# IC_Power.net
KiCad netlist of a schematic drawn in Altium Designer
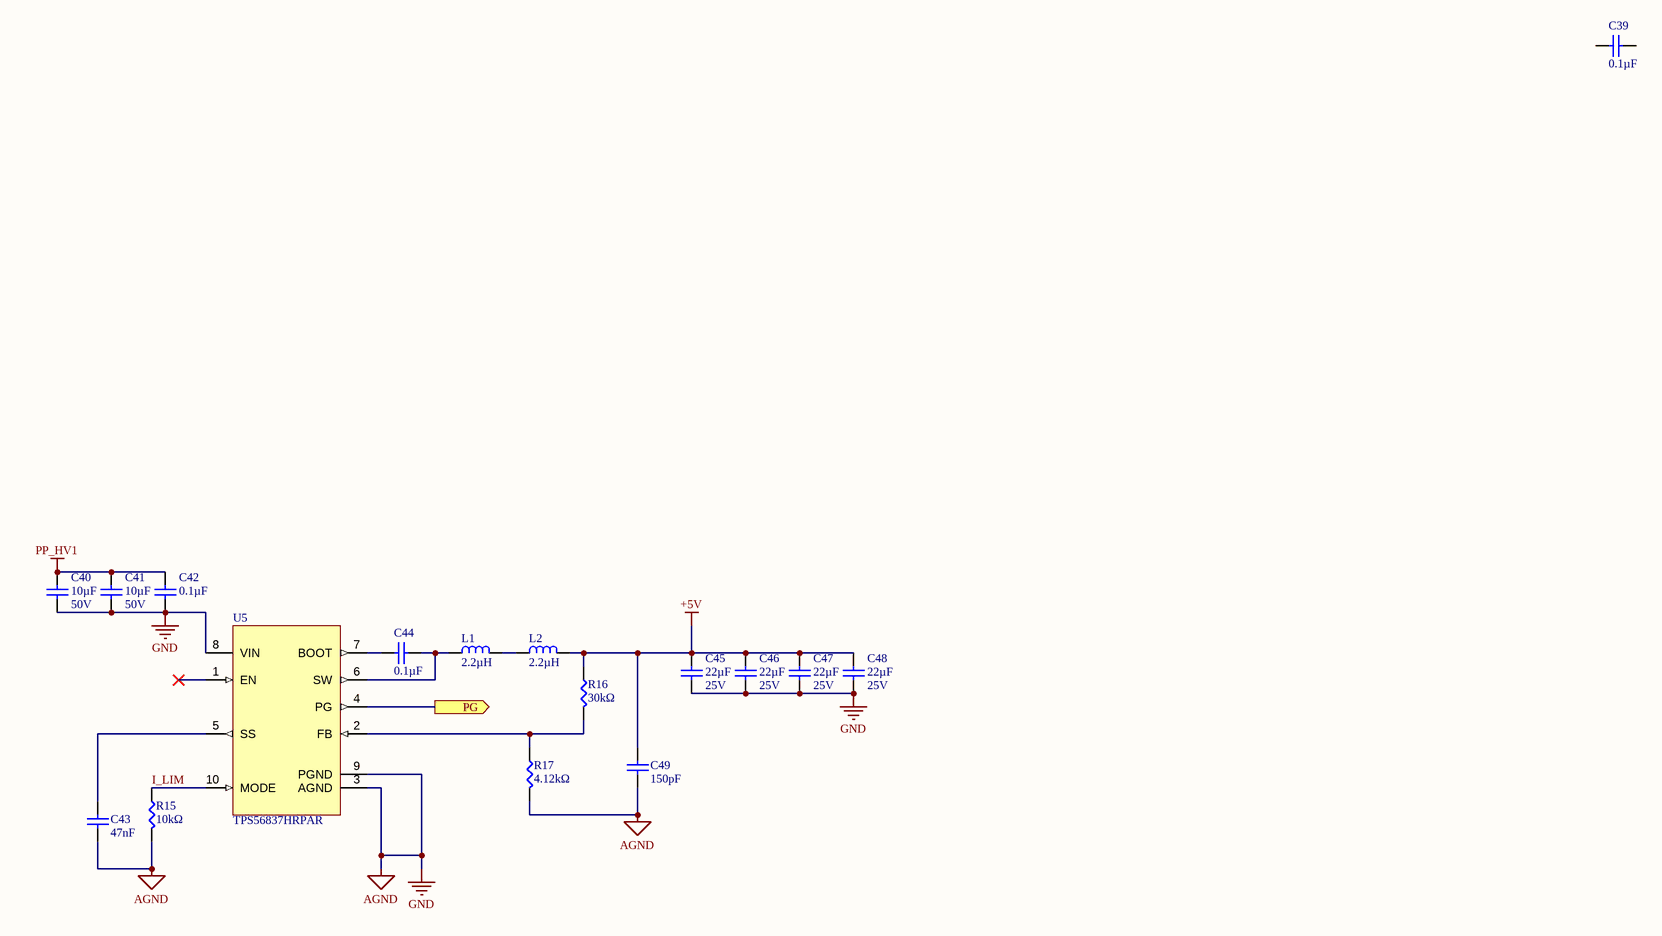
[diagram p0: IC_Power.SchDoc]

(export (version "E")
  (design (tool "Eeschema 10.0.6"))
  (components
    (comp (ref "C39")
      (value "0.1µF")
      (footprint "CAP0402")
      (description "0.1 µF ±10% 50V Ceramic Capacitor X5R 0402 (1005 Metric)")
      (fields (field (name "VOLTAGE") "50V") (field (name "Comment") "CC0402KRX5R9BB104"))
      (libsource (lib "Schlib1") (part "CC0402KRX5R9BB104"))
    )
    (comp (ref "C40")
      (value "10µF")
      (footprint "CAP1206")
      (description "10 µF ±10% 50V Ceramic Capacitor X5R 1206 (3216 Metric)")
      (fields (field (name "VOLTAGE") "50V") (field (name "Comment") "CL31A106KBHNNNE"))
      (libsource (lib "Schlib1") (part "CL31A106KBHNNNE"))
    )
    (comp (ref "C41")
      (value "10µF")
      (footprint "CAP1206")
      (description "10 µF ±10% 50V Ceramic Capacitor X5R 1206 (3216 Metric)")
      (fields (field (name "VOLTAGE") "50V") (field (name "Comment") "CL31A106KBHNNNE"))
      (libsource (lib "Schlib1") (part "CL31A106KBHNNNE"))
    )
    (comp (ref "C42")
      (value "0.1µF")
      (footprint "CAP0402")
      (description "0.1 µF ±10% 50V Ceramic Capacitor X5R 0402 (1005 Metric)")
      (fields (field (name "VOLTAGE") "50V") (field (name "Comment") "CC0402KRX5R9BB104"))
      (libsource (lib "Schlib1") (part "CC0402KRX5R9BB104"))
    )
    (comp (ref "C43")
      (value "47nF")
      (footprint "CAP0402")
      (description "0.047 µF ±10% 50V Ceramic Capacitor X7R 0402 (1005 Metric)")
      (fields (field (name "VOLTAGE") "50V") (field (name "Comment") "GRM155R71H473KE14D"))
      (libsource (lib "Schlib1") (part "GRM155R71H473KE14D"))
    )
    (comp (ref "C44")
      (value "0.1µF")
      (footprint "CAP0402")
      (description "0.1 µF ±10% 50V Ceramic Capacitor X5R 0402 (1005 Metric)")
      (fields (field (name "VOLTAGE") "50V") (field (name "Comment") "CC0402KRX5R9BB104"))
      (libsource (lib "Schlib1") (part "CC0402KRX5R9BB104"))
    )
    (comp (ref "C45")
      (value "22µF")
      (footprint "CAP0805")
      (description "22 µF ±20% 25V Ceramic Capacitor X5R 0805 (2012 Metric)")
      (fields (field (name "VOLTAGE") "25V") (field (name "Comment") "CL21A226MAYNNNE"))
      (libsource (lib "Schlib1") (part "CL21A226MAYNNNE"))
    )
    (comp (ref "C46")
      (value "22µF")
      (footprint "CAP0805")
      (description "22 µF ±20% 25V Ceramic Capacitor X5R 0805 (2012 Metric)")
      (fields (field (name "VOLTAGE") "25V") (field (name "Comment") "CL21A226MAYNNNE"))
      (libsource (lib "Schlib1") (part "CL21A226MAYNNNE"))
    )
    (comp (ref "C47")
      (value "22µF")
      (footprint "CAP0805")
      (description "22 µF ±20% 25V Ceramic Capacitor X5R 0805 (2012 Metric)")
      (fields (field (name "VOLTAGE") "25V") (field (name "Comment") "CL21A226MAYNNNE"))
      (libsource (lib "Schlib1") (part "CL21A226MAYNNNE"))
    )
    (comp (ref "C48")
      (value "22µF")
      (footprint "CAP0805")
      (description "22 µF ±20% 25V Ceramic Capacitor X5R 0805 (2012 Metric)")
      (fields (field (name "VOLTAGE") "25V") (field (name "Comment") "CL21A226MAYNNNE"))
      (libsource (lib "Schlib1") (part "CL21A226MAYNNNE"))
    )
    (comp (ref "C49")
      (value "150pF")
      (footprint "CAP0402")
      (description "150 pF ±5% 50V Ceramic Capacitor C0G, NP0 0402 (1005 Metric)")
      (fields (field (name "VOLTAGE") "50V") (field (name "Comment") "GCM1555C1H151JA16J"))
      (libsource (lib "Schlib1") (part "GCM1555C1H151JA16J"))
    )
    (comp (ref "L1")
      (value "2.2µH")
      (description "2.2 µH Shielded Molded Inductor 11.5 A 14.4mOhm Max Nonstandard")
      (fields (field (name "Comment") "AMELH6020S-2R2MT"))
      (libsource (lib "Schlib1") (part "AMELH6020S-2R2MT"))
    )
    (comp (ref "L2")
      (value "2.2µH")
      (description "2.2 µH Shielded Molded Inductor 11.5 A 14.4mOhm Max Nonstandard")
      (fields (field (name "Comment") "AMELH6020S-2R2MT"))
      (libsource (lib "Schlib1") (part "AMELH6020S-2R2MT"))
    )
    (comp (ref "R15")
      (value "10kΩ")
      (footprint "RES0402")
      (description "10 kOhms ±1% 0.063W, 1/16W Chip Resistor 0402 (1005 Metric) Moisture Resistant Thick Film")
      (fields (field (name "Comment") "RC0402FR-0710KL"))
      (libsource (lib "Schlib1") (part "RC0402FR-0710KL"))
    )
    (comp (ref "R16")
      (value "30kΩ")
      (footprint "RES0402")
      (description "30 kOhms ±1% 0.1W, 1/10W Chip Resistor 0402 (1005 Metric) Automotive AEC-Q200 Thick Film")
      (fields (field (name "Comment") "ERJ-2RKF3002X"))
      (libsource (lib "Schlib1") (part "ERJ-2RKF3002X"))
    )
    (comp (ref "R17")
      (value "4.12kΩ")
      (footprint "RES0402")
      (description "4.12 kOhms ±1% 0.063W, 1/16W Chip Resistor 0402 (1005 Metric) Automotive AEC-Q200 Thick Film")
      (fields (field (name "Comment") "RMCF0402FT4K12"))
      (libsource (lib "Schlib1") (part "RMCF0402FT4K12"))
    )
    (comp (ref "U5")
      (value "TPS56837HRPAR")
      (description "Buck Switching Regulator IC Positive Adjustable 4V 1 Output 8A 10-PowerVFQFN")
      (fields (field (name "MANUFACTURER") "Texas Instruments"))
      (libsource (lib "Schlib1") (part "TPS56837HRPAR"))
    )
  )
  (nets
    (net (code "1") (name "+5V") (class "Default")
      (node (ref "C45") (pin "2") (pinfunction "2_2") (pintype "passive"))
      (node (ref "C46") (pin "2") (pinfunction "2_2") (pintype "passive"))
      (node (ref "C47") (pin "2") (pinfunction "2_2") (pintype "passive"))
      (node (ref "C48") (pin "2") (pinfunction "2_2") (pintype "passive"))
      (node (ref "C49") (pin "2") (pinfunction "2_2") (pintype "passive"))
      (node (ref "L2") (pin "2") (pinfunction "2_2") (pintype "passive"))
      (node (ref "R16") (pin "2") (pinfunction "2_2") (pintype "passive"))
    )
    (net (code "2") (name "/I_LIM") (class "Default")
      (node (ref "R15") (pin "2") (pinfunction "2_2") (pintype "passive"))
      (node (ref "U5") (pin "10") (pinfunction "MODE_10") (pintype "input"))
    )
    (net (code "3") (name "/PG") (class "Default")
      (node (ref "U5") (pin "4") (pinfunction "PG_4") (pintype "output"))
    )
    (net (code "4") (name "AGND") (class "Default")
      (node (ref "C40") (pin "1") (pinfunction "1_1") (pintype "passive"))
      (node (ref "C41") (pin "1") (pinfunction "1_1") (pintype "passive"))
      (node (ref "C42") (pin "1") (pinfunction "1_1") (pintype "passive"))
      (node (ref "C43") (pin "1") (pinfunction "1_1") (pintype "passive"))
      (node (ref "C45") (pin "1") (pinfunction "1_1") (pintype "passive"))
      (node (ref "C46") (pin "1") (pinfunction "1_1") (pintype "passive"))
      (node (ref "C47") (pin "1") (pinfunction "1_1") (pintype "passive"))
      (node (ref "C48") (pin "1") (pinfunction "1_1") (pintype "passive"))
      (node (ref "C49") (pin "1") (pinfunction "1_1") (pintype "passive"))
      (node (ref "R15") (pin "1") (pinfunction "1_1") (pintype "passive"))
      (node (ref "R17") (pin "1") (pinfunction "1_1") (pintype "passive"))
      (node (ref "U5") (pin "3") (pinfunction "AGND_3") (pintype "passive"))
      (node (ref "U5") (pin "8") (pinfunction "VIN_8") (pintype "passive"))
      (node (ref "U5") (pin "9") (pinfunction "PGND_9") (pintype "passive"))
    )
    (net (code "5") (name "Net-(L1-Pad2)") (class "Default")
      (node (ref "L1") (pin "2") (pinfunction "2_2") (pintype "passive"))
      (node (ref "L2") (pin "1") (pinfunction "1_1") (pintype "passive"))
    )
    (net (code "6") (name "Net-(U5-BOOT)") (class "Default")
      (node (ref "C44") (pin "1") (pinfunction "1_1") (pintype "passive"))
      (node (ref "U5") (pin "7") (pinfunction "BOOT_7") (pintype "output"))
    )
    (net (code "7") (name "Net-(U5-FB)") (class "Default")
      (node (ref "R16") (pin "1") (pinfunction "1_1") (pintype "passive"))
      (node (ref "R17") (pin "2") (pinfunction "2_2") (pintype "passive"))
      (node (ref "U5") (pin "2") (pinfunction "FB_2") (pintype "input"))
    )
    (net (code "8") (name "Net-(U5-SS)") (class "Default")
      (node (ref "C43") (pin "2") (pinfunction "2_2") (pintype "passive"))
      (node (ref "U5") (pin "5") (pinfunction "SS_5") (pintype "output"))
    )
    (net (code "9") (name "Net-(U5-SW)") (class "Default")
      (node (ref "C44") (pin "2") (pinfunction "2_2") (pintype "passive"))
      (node (ref "L1") (pin "1") (pinfunction "1_1") (pintype "passive"))
      (node (ref "U5") (pin "6") (pinfunction "SW_6") (pintype "output"))
    )
    (net (code "10") (name "PP_HV1") (class "Default")
      (node (ref "C40") (pin "2") (pinfunction "2_2") (pintype "passive"))
      (node (ref "C41") (pin "2") (pinfunction "2_2") (pintype "passive"))
      (node (ref "C42") (pin "2") (pinfunction "2_2") (pintype "passive"))
    )
    (net (code "11") (name "unconnected-(C39-Pad1)") (class "Default")
      (node (ref "C39") (pin "1") (pinfunction "1_1") (pintype "passive"))
    )
    (net (code "12") (name "unconnected-(C39-Pad2)") (class "Default")
      (node (ref "C39") (pin "2") (pinfunction "2_2") (pintype "passive"))
    )
    (net (code "13") (name "unconnected-(U5-EN-Pad1)") (class "Default")
      (node (ref "U5") (pin "1") (pinfunction "EN_1") (pintype "input+no_connect"))
    )
  )
)
